# Proj_USB_GPIB.net
KiCad netlist of a schematic drawn in Altium Designer
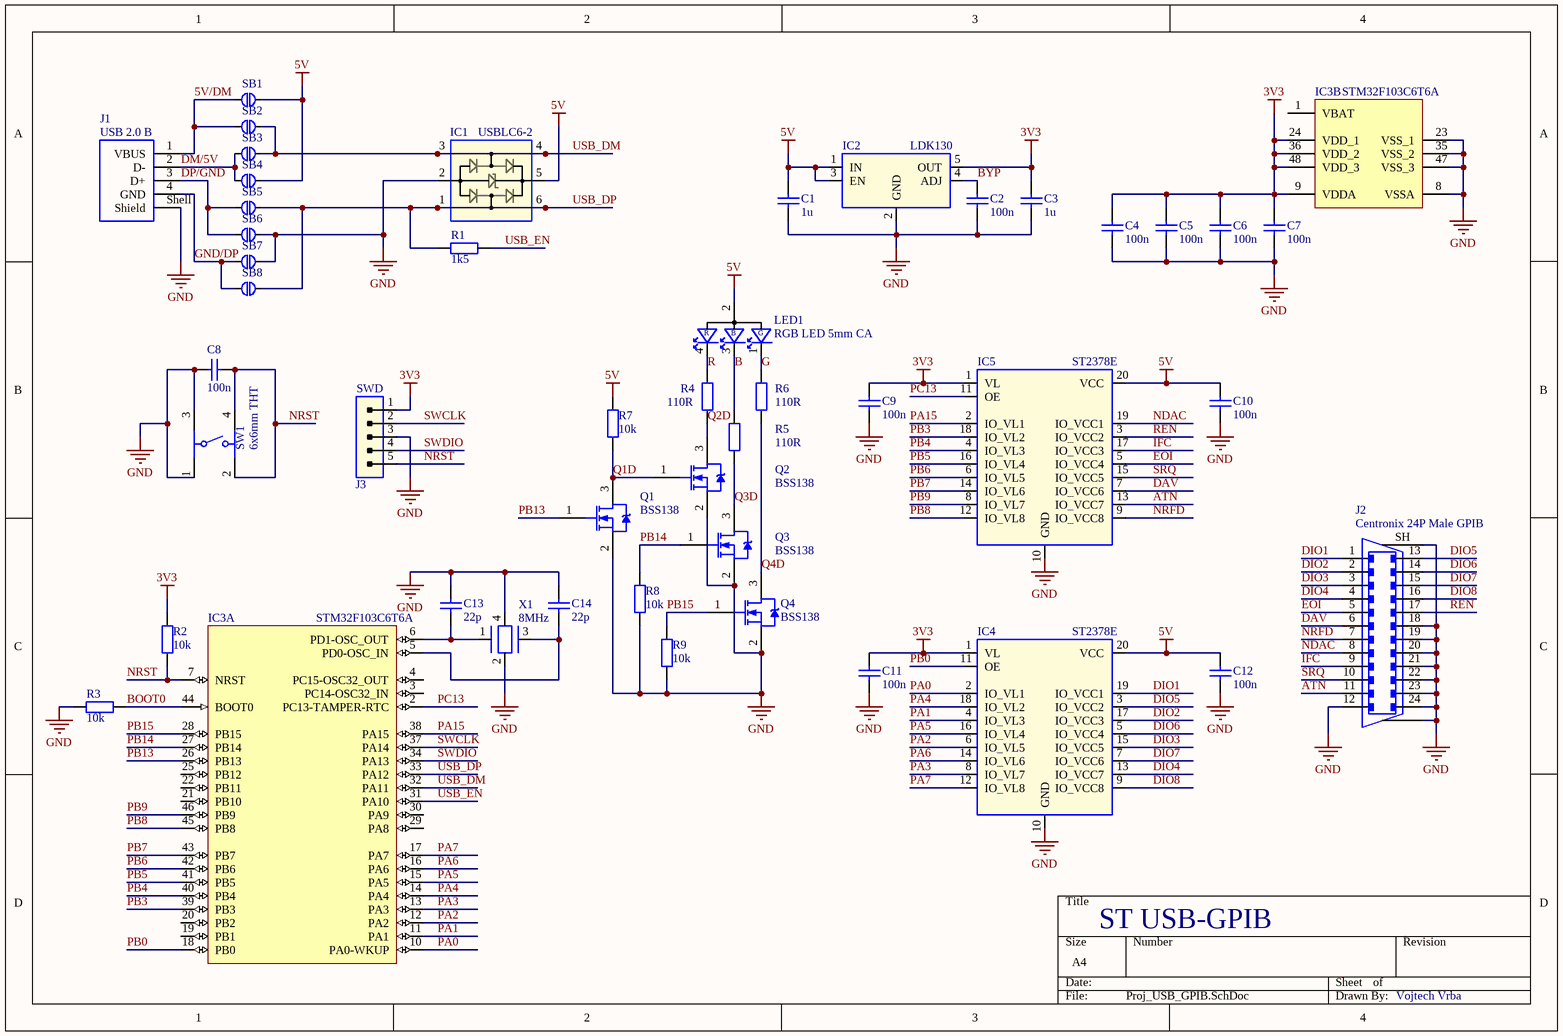
[diagram p0: Proj_USB_GPIB.SchDoc]

(export (version "E")
  (design (tool "Eeschema 10.0.6"))
  (components
    (comp (ref "C1")
      (value "1u")
      (footprint "0603")
      (description "Capacitor")
      (fields (field (name "Comment") "Cap") (field (name "PUBLISHER") "Altium Limited"))
      (libsource (lib "moje") (part "Cap"))
    )
    (comp (ref "C2")
      (value "100n")
      (footprint "0603")
      (description "Capacitor")
      (fields (field (name "Comment") "Cap") (field (name "PUBLISHER") "Altium Limited"))
      (libsource (lib "moje") (part "Cap"))
    )
    (comp (ref "C3")
      (value "1u")
      (footprint "0603")
      (description "Capacitor")
      (fields (field (name "Comment") "Cap") (field (name "PUBLISHER") "Altium Limited"))
      (libsource (lib "moje") (part "Cap"))
    )
    (comp (ref "C4")
      (value "100n")
      (footprint "0603")
      (description "Capacitor")
      (fields (field (name "Comment") "Cap") (field (name "PUBLISHER") "Altium Limited"))
      (libsource (lib "moje") (part "Cap"))
    )
    (comp (ref "C5")
      (value "100n")
      (footprint "0603")
      (description "Capacitor")
      (fields (field (name "Comment") "Cap") (field (name "PUBLISHER") "Altium Limited"))
      (libsource (lib "moje") (part "Cap"))
    )
    (comp (ref "C6")
      (value "100n")
      (footprint "0603")
      (description "Capacitor")
      (fields (field (name "Comment") "Cap") (field (name "PUBLISHER") "Altium Limited"))
      (libsource (lib "moje") (part "Cap"))
    )
    (comp (ref "C7")
      (value "100n")
      (footprint "0603")
      (description "Capacitor")
      (fields (field (name "Comment") "Cap") (field (name "PUBLISHER") "Altium Limited"))
      (libsource (lib "moje") (part "Cap"))
    )
    (comp (ref "C8")
      (value "100n")
      (footprint "0603")
      (description "Capacitor")
      (fields (field (name "Comment") "Cap") (field (name "PUBLISHER") "Altium Limited"))
      (libsource (lib "moje") (part "Cap"))
    )
    (comp (ref "C9")
      (value "100n")
      (footprint "0603")
      (description "Capacitor")
      (fields (field (name "Comment") "Cap") (field (name "PUBLISHER") "Altium Limited"))
      (libsource (lib "moje") (part "Cap"))
    )
    (comp (ref "C10")
      (value "100n")
      (footprint "0603")
      (description "Capacitor")
      (fields (field (name "Comment") "Cap") (field (name "PUBLISHER") "Altium Limited"))
      (libsource (lib "moje") (part "Cap"))
    )
    (comp (ref "C11")
      (value "100n")
      (footprint "0603")
      (description "Capacitor")
      (fields (field (name "Comment") "Cap") (field (name "PUBLISHER") "Altium Limited"))
      (libsource (lib "moje") (part "Cap"))
    )
    (comp (ref "C12")
      (value "100n")
      (footprint "0603")
      (description "Capacitor")
      (fields (field (name "Comment") "Cap") (field (name "PUBLISHER") "Altium Limited"))
      (libsource (lib "moje") (part "Cap"))
    )
    (comp (ref "C13")
      (value "22p")
      (footprint "0603")
      (description "Capacitor")
      (fields (field (name "Comment") "Cap") (field (name "PUBLISHER") "Altium Limited"))
      (libsource (lib "moje") (part "Cap"))
    )
    (comp (ref "C14")
      (value "22p")
      (footprint "0603")
      (description "Capacitor")
      (fields (field (name "Comment") "Cap") (field (name "PUBLISHER") "Altium Limited"))
      (libsource (lib "moje") (part "Cap"))
    )
    (comp (ref "IC1")
      (value "USBLC6-2")
      (footprint "SOT23-6")
      (description "Very low capacitance ESD protection diode array")
      (libsource (lib "moje") (part "USBLC6-2"))
    )
    (comp (ref "IC2")
      (value "LDK130")
      (footprint "SOT23-5")
      (description "300 mA low quiescent current very low noise LDO")
      (libsource (lib "moje") (part "LDK130"))
    )
    (comp (ref "IC3")
      (value "STM32F103C6T6A")
      (footprint "STM-LQFP48_L")
      (libsource (lib "STMicroelectronics STM32 F1") (part "STM32F103C6T6A"))
    )
    (comp (ref "IC4")
      (value "ST2378E")
      (footprint "TSSOP20")
      (description "8-bit dual supply 1.71 V to 5.5 V level translator  with I/O VCC ±15 kV ESD protection")
      (libsource (lib "moje") (part "ST2378E"))
    )
    (comp (ref "IC5")
      (value "ST2378E")
      (footprint "TSSOP20")
      (description "8-bit dual supply 1.71 V to 5.5 V level translator  with I/O VCC ±15 kV ESD protection")
      (libsource (lib "moje") (part "ST2378E"))
    )
    (comp (ref "J1")
      (value "USB 2.0 B")
      (footprint "61400416121")
      (description "USB 2.0 Type B, Receptacle, Horizontal, THT")
      (fields
        (field (name "MANUFACTURER") "Wurth Elektronik")
        (field (name "MANUFACTURER PART NUMBER") "61400416121")
      )
      (libsource (lib "WR-USB (rev21a)") (part "61400416121"))
    )
    (comp (ref "J2")
      (value "Centronix 24P Male GPIB")
      (footprint "Norcomp-112-024-213R001")
      (description "Centronix 24P Male THT GPIB Connector, Farnell 2421095")
      (libsource (lib "moje") (part "Centronix 24P Male GPIB"))
    )
    (comp (ref "J3")
      (value "SWD")
      (footprint "PIN_HEADER_5P")
      (libsource (lib "moje") (part "Pin Header 5P"))
    )
    (comp (ref "LED1")
      (value "RGB LED 5mm CA")
      (footprint "RGB_LED_5mm")
      (description "5mm RGB LED Common Anode, eg. OSTHMA5B61A")
      (libsource (lib "moje") (part "RGB LED 5mm CA"))
    )
    (comp (ref "Q1")
      (value "BSS138")
      (footprint "SOT23-3")
      (description "MOSFET SOT-23 N-CH LOGIC LEVEL")
      (fields (field (name "PUBLISHER") "Altium Limited"))
      (libsource (lib "moje") (part "BSS138"))
    )
    (comp (ref "Q2")
      (value "BSS138")
      (footprint "SOT23-3")
      (description "MOSFET SOT-23 N-CH LOGIC LEVEL")
      (fields (field (name "PUBLISHER") "Altium Limited"))
      (libsource (lib "moje") (part "BSS138"))
    )
    (comp (ref "Q3")
      (value "BSS138")
      (footprint "SOT23-3")
      (description "MOSFET SOT-23 N-CH LOGIC LEVEL")
      (fields (field (name "PUBLISHER") "Altium Limited"))
      (libsource (lib "moje") (part "BSS138"))
    )
    (comp (ref "Q4")
      (value "BSS138")
      (footprint "SOT23-3")
      (description "MOSFET SOT-23 N-CH LOGIC LEVEL")
      (fields (field (name "PUBLISHER") "Altium Limited"))
      (libsource (lib "moje") (part "BSS138"))
    )
    (comp (ref "R1")
      (value "1k5")
      (footprint "0603")
      (description "Resistor")
      (fields (field (name "Comment") "Res") (field (name "PUBLISHER") "Altium Limited"))
      (libsource (lib "") (part "Res_3"))
    )
    (comp (ref "R2")
      (value "10k")
      (footprint "0603")
      (description "Resistor")
      (fields (field (name "Comment") "Res") (field (name "PUBLISHER") "Altium Limited"))
      (libsource (lib "") (part "Res_2"))
    )
    (comp (ref "R3")
      (value "10k")
      (footprint "0603")
      (description "Resistor")
      (fields (field (name "Comment") "Res") (field (name "PUBLISHER") "Altium Limited"))
      (libsource (lib "") (part "Res_1"))
    )
    (comp (ref "R4")
      (value "110R")
      (footprint "0603")
      (description "Resistor")
      (fields (field (name "Comment") "Res") (field (name "PUBLISHER") "Altium Limited"))
      (libsource (lib "") (part "Res_1"))
    )
    (comp (ref "R5")
      (value "110R")
      (footprint "0603")
      (description "Resistor")
      (fields (field (name "Comment") "Res") (field (name "PUBLISHER") "Altium Limited"))
      (libsource (lib "moje") (part "Res"))
    )
    (comp (ref "R6")
      (value "110R")
      (footprint "0603")
      (description "Resistor")
      (fields (field (name "Comment") "Res") (field (name "PUBLISHER") "Altium Limited"))
      (libsource (lib "moje") (part "Res"))
    )
    (comp (ref "R7")
      (value "10k")
      (footprint "0603")
      (description "Resistor")
      (fields (field (name "Comment") "Res") (field (name "PUBLISHER") "Altium Limited"))
      (libsource (lib "") (part "Res_2"))
    )
    (comp (ref "R8")
      (value "10k")
      (footprint "0603")
      (description "Resistor")
      (fields (field (name "Comment") "Res") (field (name "PUBLISHER") "Altium Limited"))
      (libsource (lib "") (part "Res_2"))
    )
    (comp (ref "R9")
      (value "10k")
      (footprint "0603")
      (description "Resistor")
      (fields (field (name "Comment") "Res") (field (name "PUBLISHER") "Altium Limited"))
      (libsource (lib "") (part "Res_2"))
    )
    (comp (ref "SB1") (value "SHORT_CON2") (footprint "0402") (libsource (lib "moje") (part "SHORT_CON2")))
    (comp (ref "SB2") (value "SHORT_CON2") (footprint "0402") (libsource (lib "moje") (part "SHORT_CON2")))
    (comp (ref "SB3") (value "SHORT_CON2") (footprint "0402") (libsource (lib "moje") (part "SHORT_CON2")))
    (comp (ref "SB4") (value "SHORT_CON2") (footprint "0402") (libsource (lib "moje") (part "SHORT_CON2")))
    (comp (ref "SB5") (value "SHORT_CON2") (footprint "0402") (libsource (lib "moje") (part "SHORT_CON2")))
    (comp (ref "SB6") (value "SHORT_CON2") (footprint "0402") (libsource (lib "moje") (part "SHORT_CON2")))
    (comp (ref "SB7") (value "SHORT_CON2") (footprint "0402") (libsource (lib "moje") (part "SHORT_CON2")))
    (comp (ref "SB8") (value "SHORT_CON2") (footprint "0402") (libsource (lib "moje") (part "SHORT_CON2")))
    (comp (ref "SW1")
      (value "6x6mm THT")
      (footprint "4301x60957x6")
      (description "WS-TATV THT Tact Switch 6x6mm, height 9.5mm, 160gf")
      (fields (field (name "PART NUMBER") "430186095716") (field (name "PUBLISHER") "Wurth Elektronik"))
      (libsource (lib "WS-TATV (rev19a)") (part "430186095716"))
    )
    (comp (ref "X1") (value "8MHz") (footprint "CRYSTAL_5x3.2mm") (libsource (lib "moje") (part "Crystal")))
  )
  (nets
    (net (code "1") (name "/5V{slash}DM") (class "Default")
      (node (ref "J1") (pin "1") (pinfunction "VBUS_1") (pintype "passive"))
      (node (ref "SB1") (pin "1") (pinfunction "1_1") (pintype "passive"))
      (node (ref "SB2") (pin "1") (pinfunction "1_1") (pintype "passive"))
    )
    (net (code "2") (name "/ATN") (class "Default")
      (node (ref "IC5") (pin "13") (pinfunction "IO_VCC7_13") (pintype "passive"))
      (node (ref "J2") (pin "11") (pinfunction "11_11") (pintype "passive"))
    )
    (net (code "3") (name "/B") (class "Default")
      (node (ref "LED1") (pin "3") (pinfunction "B_3") (pintype "passive"))
      (node (ref "R5") (pin "1") (pinfunction "1_1") (pintype "passive"))
    )
    (net (code "4") (name "/BOOT0") (class "Default")
      (node (ref "IC3") (pin "44") (pinfunction "BOOT0_44") (pintype "input"))
      (node (ref "R3") (pin "1") (pinfunction "1_1") (pintype "passive"))
    )
    (net (code "5") (name "/BYP") (class "Default")
      (node (ref "C2") (pin "1") (pinfunction "1_1") (pintype "passive"))
      (node (ref "IC2") (pin "4") (pinfunction "ADJ_4") (pintype "passive"))
    )
    (net (code "6") (name "/DAV") (class "Default")
      (node (ref "IC5") (pin "7") (pinfunction "IO_VCC6_7") (pintype "passive"))
      (node (ref "J2") (pin "6") (pinfunction "6_6") (pintype "passive"))
    )
    (net (code "7") (name "/DIO1") (class "Default")
      (node (ref "IC4") (pin "19") (pinfunction "IO_VCC1_19") (pintype "passive"))
      (node (ref "J2") (pin "1") (pinfunction "0_1") (pintype "passive"))
    )
    (net (code "8") (name "/DIO2") (class "Default")
      (node (ref "IC4") (pin "17") (pinfunction "IO_VCC3_17") (pintype "passive"))
      (node (ref "J2") (pin "2") (pinfunction "2_2") (pintype "passive"))
    )
    (net (code "9") (name "/DIO3") (class "Default")
      (node (ref "IC4") (pin "15") (pinfunction "IO_VCC5_15") (pintype "passive"))
      (node (ref "J2") (pin "3") (pinfunction "3_3") (pintype "passive"))
    )
    (net (code "10") (name "/DIO4") (class "Default")
      (node (ref "IC4") (pin "13") (pinfunction "IO_VCC7_13") (pintype "passive"))
      (node (ref "J2") (pin "4") (pinfunction "4_4") (pintype "passive"))
    )
    (net (code "11") (name "/DIO5") (class "Default")
      (node (ref "IC4") (pin "3") (pinfunction "IO_VCC2_3") (pintype "passive"))
      (node (ref "J2") (pin "13") (pinfunction "13_13") (pintype "passive"))
    )
    (net (code "12") (name "/DIO6") (class "Default")
      (node (ref "IC4") (pin "5") (pinfunction "IO_VCC4_5") (pintype "passive"))
      (node (ref "J2") (pin "14") (pinfunction "14_14") (pintype "passive"))
    )
    (net (code "13") (name "/DIO7") (class "Default")
      (node (ref "IC4") (pin "7") (pinfunction "IO_VCC6_7") (pintype "passive"))
      (node (ref "J2") (pin "15") (pinfunction "15_15") (pintype "passive"))
    )
    (net (code "14") (name "/DIO8") (class "Default")
      (node (ref "IC4") (pin "9") (pinfunction "IO_VCC8_9") (pintype "passive"))
      (node (ref "J2") (pin "16") (pinfunction "16_16") (pintype "passive"))
    )
    (net (code "15") (name "/DM{slash}5V") (class "Default")
      (node (ref "J1") (pin "2") (pinfunction "D-_2") (pintype "passive"))
      (node (ref "SB3") (pin "1") (pinfunction "1_1") (pintype "passive"))
      (node (ref "SB4") (pin "1") (pinfunction "1_1") (pintype "passive"))
    )
    (net (code "16") (name "/DP{slash}GND") (class "Default")
      (node (ref "J1") (pin "3") (pinfunction "D+_3") (pintype "passive"))
      (node (ref "SB5") (pin "1") (pinfunction "1_1") (pintype "passive"))
      (node (ref "SB6") (pin "1") (pinfunction "1_1") (pintype "passive"))
    )
    (net (code "17") (name "/EOI") (class "Default")
      (node (ref "IC5") (pin "5") (pinfunction "IO_VCC4_5") (pintype "passive"))
      (node (ref "J2") (pin "5") (pinfunction "5_5") (pintype "passive"))
    )
    (net (code "18") (name "/G") (class "Default")
      (node (ref "LED1") (pin "1") (pinfunction "G_1") (pintype "passive"))
      (node (ref "R6") (pin "1") (pinfunction "1_1") (pintype "passive"))
    )
    (net (code "19") (name "/GND{slash}DP") (class "Default")
      (node (ref "J1") (pin "4") (pinfunction "GND_4") (pintype "passive"))
      (node (ref "SB7") (pin "1") (pinfunction "1_1") (pintype "passive"))
      (node (ref "SB8") (pin "1") (pinfunction "1_1") (pintype "passive"))
    )
    (net (code "20") (name "/IFC") (class "Default")
      (node (ref "IC5") (pin "17") (pinfunction "IO_VCC3_17") (pintype "passive"))
      (node (ref "J2") (pin "9") (pinfunction "9_9") (pintype "passive"))
    )
    (net (code "21") (name "/NDAC") (class "Default")
      (node (ref "IC5") (pin "19") (pinfunction "IO_VCC1_19") (pintype "passive"))
      (node (ref "J2") (pin "8") (pinfunction "8_8") (pintype "passive"))
    )
    (net (code "22") (name "/NRFD") (class "Default")
      (node (ref "IC5") (pin "9") (pinfunction "IO_VCC8_9") (pintype "passive"))
      (node (ref "J2") (pin "7") (pinfunction "7_7") (pintype "passive"))
    )
    (net (code "23") (name "/NRST") (class "Default")
      (node (ref "C8") (pin "2") (pinfunction "2_2") (pintype "passive"))
      (node (ref "IC3") (pin "7") (pinfunction "NRST_7") (pintype "bidirectional"))
      (node (ref "J3") (pin "5") (pinfunction "0_5") (pintype "passive"))
      (node (ref "R2") (pin "1") (pinfunction "1_1") (pintype "passive"))
      (node (ref "SW1") (pin "2") (pinfunction "2_2") (pintype "passive"))
      (node (ref "SW1") (pin "4") (pinfunction "4_4") (pintype "passive"))
    )
    (net (code "24") (name "/PA0") (class "Default")
      (node (ref "IC3") (pin "10") (pinfunction "PA0-WKUP_10") (pintype "bidirectional"))
      (node (ref "IC4") (pin "2") (pinfunction "IO_VL1_2") (pintype "passive"))
    )
    (net (code "25") (name "/PA1") (class "Default")
      (node (ref "IC3") (pin "11") (pinfunction "PA1_11") (pintype "bidirectional"))
      (node (ref "IC4") (pin "4") (pinfunction "IO_VL3_4") (pintype "passive"))
    )
    (net (code "26") (name "/PA2") (class "Default")
      (node (ref "IC3") (pin "12") (pinfunction "PA2_12") (pintype "bidirectional"))
      (node (ref "IC4") (pin "6") (pinfunction "IO_VL5_6") (pintype "passive"))
    )
    (net (code "27") (name "/PA3") (class "Default")
      (node (ref "IC3") (pin "13") (pinfunction "PA3_13") (pintype "bidirectional"))
      (node (ref "IC4") (pin "8") (pinfunction "IO_VL7_8") (pintype "passive"))
    )
    (net (code "28") (name "/PA4") (class "Default")
      (node (ref "IC3") (pin "14") (pinfunction "PA4_14") (pintype "bidirectional"))
      (node (ref "IC4") (pin "18") (pinfunction "IO_VL2_18") (pintype "passive"))
    )
    (net (code "29") (name "/PA5") (class "Default")
      (node (ref "IC3") (pin "15") (pinfunction "PA5_15") (pintype "bidirectional"))
      (node (ref "IC4") (pin "16") (pinfunction "IO_VL4_16") (pintype "passive"))
    )
    (net (code "30") (name "/PA6") (class "Default")
      (node (ref "IC3") (pin "16") (pinfunction "PA6_16") (pintype "bidirectional"))
      (node (ref "IC4") (pin "14") (pinfunction "IO_VL6_14") (pintype "passive"))
    )
    (net (code "31") (name "/PA7") (class "Default")
      (node (ref "IC3") (pin "17") (pinfunction "PA7_17") (pintype "bidirectional"))
      (node (ref "IC4") (pin "12") (pinfunction "IO_VL8_12") (pintype "passive"))
    )
    (net (code "32") (name "/PA15") (class "Default")
      (node (ref "IC3") (pin "38") (pinfunction "PA15_38") (pintype "bidirectional"))
      (node (ref "IC5") (pin "2") (pinfunction "IO_VL1_2") (pintype "passive"))
    )
    (net (code "33") (name "/PB0") (class "Default")
      (node (ref "IC3") (pin "18") (pinfunction "PB0_18") (pintype "bidirectional"))
      (node (ref "IC4") (pin "11") (pinfunction "OE_11") (pintype "passive"))
    )
    (net (code "34") (name "/PB3") (class "Default")
      (node (ref "IC3") (pin "39") (pinfunction "PB3_39") (pintype "bidirectional"))
      (node (ref "IC5") (pin "18") (pinfunction "IO_VL2_18") (pintype "passive"))
    )
    (net (code "35") (name "/PB4") (class "Default")
      (node (ref "IC3") (pin "40") (pinfunction "PB4_40") (pintype "bidirectional"))
      (node (ref "IC5") (pin "4") (pinfunction "IO_VL3_4") (pintype "passive"))
    )
    (net (code "36") (name "/PB5") (class "Default")
      (node (ref "IC3") (pin "41") (pinfunction "PB5_41") (pintype "bidirectional"))
      (node (ref "IC5") (pin "16") (pinfunction "IO_VL4_16") (pintype "passive"))
    )
    (net (code "37") (name "/PB6") (class "Default")
      (node (ref "IC3") (pin "42") (pinfunction "PB6_42") (pintype "bidirectional"))
      (node (ref "IC5") (pin "6") (pinfunction "IO_VL5_6") (pintype "passive"))
    )
    (net (code "38") (name "/PB7") (class "Default")
      (node (ref "IC3") (pin "43") (pinfunction "PB7_43") (pintype "bidirectional"))
      (node (ref "IC5") (pin "14") (pinfunction "IO_VL6_14") (pintype "passive"))
    )
    (net (code "39") (name "/PB8") (class "Default")
      (node (ref "IC3") (pin "45") (pinfunction "PB8_45") (pintype "bidirectional"))
      (node (ref "IC5") (pin "12") (pinfunction "IO_VL8_12") (pintype "passive"))
    )
    (net (code "40") (name "/PB9") (class "Default")
      (node (ref "IC3") (pin "46") (pinfunction "PB9_46") (pintype "bidirectional"))
      (node (ref "IC5") (pin "8") (pinfunction "IO_VL7_8") (pintype "passive"))
    )
    (net (code "41") (name "/PB13") (class "Default")
      (node (ref "IC3") (pin "26") (pinfunction "PB13_26") (pintype "bidirectional"))
      (node (ref "Q1") (pin "1") (pinfunction "G_1") (pintype "passive"))
    )
    (net (code "42") (name "/PB14") (class "Default")
      (node (ref "IC3") (pin "27") (pinfunction "PB14_27") (pintype "bidirectional"))
      (node (ref "Q3") (pin "1") (pinfunction "G_1") (pintype "passive"))
      (node (ref "R8") (pin "2") (pinfunction "2_2") (pintype "passive"))
    )
    (net (code "43") (name "/PB15") (class "Default")
      (node (ref "IC3") (pin "28") (pinfunction "PB15_28") (pintype "bidirectional"))
      (node (ref "Q4") (pin "1") (pinfunction "G_1") (pintype "passive"))
      (node (ref "R9") (pin "2") (pinfunction "2_2") (pintype "passive"))
    )
    (net (code "44") (name "/PC13") (class "Default")
      (node (ref "IC3") (pin "2") (pinfunction "PC13-TAMPER-RTC_2") (pintype "bidirectional"))
      (node (ref "IC5") (pin "11") (pinfunction "OE_11") (pintype "passive"))
    )
    (net (code "45") (name "/Q1D") (class "Default")
      (node (ref "Q1") (pin "3") (pinfunction "D_3") (pintype "passive"))
      (node (ref "Q2") (pin "1") (pinfunction "G_1") (pintype "passive"))
      (node (ref "R7") (pin "1") (pinfunction "1_1") (pintype "passive"))
    )
    (net (code "46") (name "/Q2D") (class "Default")
      (node (ref "Q2") (pin "3") (pinfunction "D_3") (pintype "passive"))
      (node (ref "R4") (pin "2") (pinfunction "2_2") (pintype "passive"))
    )
    (net (code "47") (name "/Q3D") (class "Default")
      (node (ref "Q3") (pin "3") (pinfunction "D_3") (pintype "passive"))
      (node (ref "R5") (pin "2") (pinfunction "2_2") (pintype "passive"))
    )
    (net (code "48") (name "/Q4D") (class "Default")
      (node (ref "Q4") (pin "3") (pinfunction "D_3") (pintype "passive"))
      (node (ref "R6") (pin "2") (pinfunction "2_2") (pintype "passive"))
    )
    (net (code "49") (name "/R") (class "Default")
      (node (ref "LED1") (pin "4") (pinfunction "R_4") (pintype "passive"))
      (node (ref "R4") (pin "1") (pinfunction "1_1") (pintype "passive"))
    )
    (net (code "50") (name "/REN") (class "Default")
      (node (ref "IC5") (pin "3") (pinfunction "IO_VCC2_3") (pintype "passive"))
      (node (ref "J2") (pin "17") (pinfunction "17_17") (pintype "passive"))
    )
    (net (code "51") (name "/SRQ") (class "Default")
      (node (ref "IC5") (pin "15") (pinfunction "IO_VCC5_15") (pintype "passive"))
      (node (ref "J2") (pin "10") (pinfunction "10_10") (pintype "passive"))
    )
    (net (code "52") (name "/SWCLK") (class "Default")
      (node (ref "IC3") (pin "37") (pinfunction "PA14_37") (pintype "bidirectional"))
      (node (ref "J3") (pin "2") (pinfunction "0_2") (pintype "passive"))
    )
    (net (code "53") (name "/SWDIO") (class "Default")
      (node (ref "IC3") (pin "34") (pinfunction "PA13_34") (pintype "bidirectional"))
      (node (ref "J3") (pin "4") (pinfunction "0_4") (pintype "passive"))
    )
    (net (code "54") (name "/USB_DM") (class "Default")
      (node (ref "IC1") (pin "3") (pinfunction "IO_3") (pintype "passive"))
      (node (ref "IC1") (pin "4") (pinfunction "IO_4") (pintype "passive"))
      (node (ref "IC3") (pin "32") (pinfunction "PA11_32") (pintype "bidirectional"))
      (node (ref "SB2") (pin "2") (pinfunction "2_2") (pintype "passive"))
      (node (ref "SB3") (pin "2") (pinfunction "2_2") (pintype "passive"))
    )
    (net (code "55") (name "/USB_DP") (class "Default")
      (node (ref "IC1") (pin "1") (pinfunction "IO_1") (pintype "passive"))
      (node (ref "IC1") (pin "6") (pinfunction "IO_6") (pintype "passive"))
      (node (ref "IC3") (pin "33") (pinfunction "PA12_33") (pintype "bidirectional"))
      (node (ref "R1") (pin "1") (pinfunction "1_1") (pintype "passive"))
      (node (ref "SB5") (pin "2") (pinfunction "2_2") (pintype "passive"))
      (node (ref "SB8") (pin "2") (pinfunction "2_2") (pintype "passive"))
    )
    (net (code "56") (name "/USB_EN") (class "Default")
      (node (ref "IC3") (pin "31") (pinfunction "PA10_31") (pintype "bidirectional"))
      (node (ref "R1") (pin "2") (pinfunction "2_2") (pintype "passive"))
    )
    (net (code "57") (name "3V3") (class "Default")
      (node (ref "C11") (pin "1") (pinfunction "1_1") (pintype "passive"))
      (node (ref "C3") (pin "1") (pinfunction "1_1") (pintype "passive"))
      (node (ref "C4") (pin "1") (pinfunction "1_1") (pintype "passive"))
      (node (ref "C5") (pin "1") (pinfunction "1_1") (pintype "passive"))
      (node (ref "C6") (pin "1") (pinfunction "1_1") (pintype "passive"))
      (node (ref "C7") (pin "1") (pinfunction "1_1") (pintype "passive"))
      (node (ref "C9") (pin "1") (pinfunction "1_1") (pintype "passive"))
      (node (ref "IC2") (pin "5") (pinfunction "OUT_5") (pintype "passive"))
      (node (ref "IC3") (pin "24") (pinfunction "VDD_1_24") (pintype "power_in"))
      (node (ref "IC3") (pin "36") (pinfunction "VDD_2_36") (pintype "power_in"))
      (node (ref "IC3") (pin "48") (pinfunction "VDD_3_48") (pintype "power_in"))
      (node (ref "IC3") (pin "9") (pinfunction "VDDA_9") (pintype "power_in"))
      (node (ref "IC4") (pin "1") (pinfunction "VL_1") (pintype "passive"))
      (node (ref "IC5") (pin "1") (pinfunction "VL_1") (pintype "passive"))
      (node (ref "J3") (pin "1") (pinfunction "0_1") (pintype "passive"))
      (node (ref "R2") (pin "2") (pinfunction "2_2") (pintype "passive"))
    )
    (net (code "58") (name "5V") (class "Default")
      (node (ref "C1") (pin "1") (pinfunction "1_1") (pintype "passive"))
      (node (ref "C10") (pin "1") (pinfunction "1_1") (pintype "passive"))
      (node (ref "C12") (pin "1") (pinfunction "1_1") (pintype "passive"))
      (node (ref "IC1") (pin "5") (pinfunction "VP_5") (pintype "passive"))
      (node (ref "IC2") (pin "1") (pinfunction "IN_1") (pintype "passive"))
      (node (ref "IC2") (pin "3") (pinfunction "EN_3") (pintype "passive"))
      (node (ref "IC4") (pin "20") (pinfunction "VCC_20") (pintype "passive"))
      (node (ref "IC5") (pin "20") (pinfunction "VCC_20") (pintype "passive"))
      (node (ref "LED1") (pin "2") (pinfunction "A_2") (pintype "passive"))
      (node (ref "R7") (pin "2") (pinfunction "2_2") (pintype "passive"))
      (node (ref "SB1") (pin "2") (pinfunction "2_2") (pintype "passive"))
      (node (ref "SB4") (pin "2") (pinfunction "2_2") (pintype "passive"))
    )
    (net (code "59") (name "GND") (class "Default")
      (node (ref "C1") (pin "2") (pinfunction "2_2") (pintype "passive"))
      (node (ref "C10") (pin "2") (pinfunction "2_2") (pintype "passive"))
      (node (ref "C11") (pin "2") (pinfunction "2_2") (pintype "passive"))
      (node (ref "C12") (pin "2") (pinfunction "2_2") (pintype "passive"))
      (node (ref "C13") (pin "2") (pinfunction "2_2") (pintype "passive"))
      (node (ref "C14") (pin "2") (pinfunction "2_2") (pintype "passive"))
      (node (ref "C2") (pin "2") (pinfunction "2_2") (pintype "passive"))
      (node (ref "C3") (pin "2") (pinfunction "2_2") (pintype "passive"))
      (node (ref "C4") (pin "2") (pinfunction "2_2") (pintype "passive"))
      (node (ref "C5") (pin "2") (pinfunction "2_2") (pintype "passive"))
      (node (ref "C6") (pin "2") (pinfunction "2_2") (pintype "passive"))
      (node (ref "C7") (pin "2") (pinfunction "2_2") (pintype "passive"))
      (node (ref "C8") (pin "1") (pinfunction "1_1") (pintype "passive"))
      (node (ref "C9") (pin "2") (pinfunction "2_2") (pintype "passive"))
      (node (ref "IC1") (pin "2") (pinfunction "VN_2") (pintype "passive"))
      (node (ref "IC2") (pin "2") (pinfunction "GND_2") (pintype "passive"))
      (node (ref "IC3") (pin "23") (pinfunction "VSS_1_23") (pintype "power_in"))
      (node (ref "IC3") (pin "35") (pinfunction "VSS_2_35") (pintype "power_in"))
      (node (ref "IC3") (pin "47") (pinfunction "VSS_3_47") (pintype "power_in"))
      (node (ref "IC3") (pin "8") (pinfunction "VSSA_8") (pintype "power_in"))
      (node (ref "IC4") (pin "10") (pinfunction "GND_10") (pintype "passive"))
      (node (ref "IC5") (pin "10") (pinfunction "GND_10") (pintype "passive"))
      (node (ref "J1") (pin "Shell") (pinfunction "Shield_Shell") (pintype "passive"))
      (node (ref "J2") (pin "12") (pinfunction "12_12") (pintype "passive"))
      (node (ref "J2") (pin "18") (pinfunction "18_18") (pintype "passive"))
      (node (ref "J2") (pin "19") (pinfunction "19_19") (pintype "passive"))
      (node (ref "J2") (pin "20") (pinfunction "20_20") (pintype "passive"))
      (node (ref "J2") (pin "21") (pinfunction "21_21") (pintype "passive"))
      (node (ref "J2") (pin "22") (pinfunction "22_22") (pintype "passive"))
      (node (ref "J2") (pin "23") (pinfunction "23_23") (pintype "passive"))
      (node (ref "J2") (pin "24") (pinfunction "24_24") (pintype "passive"))
      (node (ref "J2") (pin "SH") (pinfunction "SH_SH") (pintype "passive"))
      (node (ref "J3") (pin "3") (pinfunction "0_3") (pintype "passive"))
      (node (ref "Q1") (pin "2") (pinfunction "S_2") (pintype "passive"))
      (node (ref "Q2") (pin "2") (pinfunction "S_2") (pintype "passive"))
      (node (ref "Q3") (pin "2") (pinfunction "S_2") (pintype "passive"))
      (node (ref "Q4") (pin "2") (pinfunction "S_2") (pintype "passive"))
      (node (ref "R3") (pin "2") (pinfunction "2_2") (pintype "passive"))
      (node (ref "R8") (pin "1") (pinfunction "1_1") (pintype "passive"))
      (node (ref "R9") (pin "1") (pinfunction "1_1") (pintype "passive"))
      (node (ref "SB6") (pin "2") (pinfunction "2_2") (pintype "passive"))
      (node (ref "SB7") (pin "2") (pinfunction "2_2") (pintype "passive"))
      (node (ref "SW1") (pin "1") (pinfunction "1_1") (pintype "passive"))
      (node (ref "SW1") (pin "3") (pinfunction "3_3") (pintype "passive"))
      (node (ref "X1") (pin "2") (pinfunction "2_2") (pintype "passive"))
      (node (ref "X1") (pin "4") (pinfunction "4_4") (pintype "passive"))
    )
    (net (code "60") (name "Net-(IC3A-PD0-OSC_IN)") (class "Default")
      (node (ref "C14") (pin "1") (pinfunction "1_1") (pintype "passive"))
      (node (ref "IC3") (pin "5") (pinfunction "PD0-OSC_IN_5") (pintype "bidirectional"))
      (node (ref "X1") (pin "3") (pinfunction "3_3") (pintype "passive"))
    )
    (net (code "61") (name "Net-(IC3A-PD1-OSC_OUT)") (class "Default")
      (node (ref "C13") (pin "1") (pinfunction "1_1") (pintype "passive"))
      (node (ref "IC3") (pin "6") (pinfunction "PD1-OSC_OUT_6") (pintype "bidirectional"))
      (node (ref "X1") (pin "1") (pinfunction "1_1") (pintype "passive"))
    )
    (net (code "62") (name "unconnected-(IC3A-PA8-Pad29)") (class "Default")
      (node (ref "IC3") (pin "29") (pinfunction "PA8_29") (pintype "bidirectional"))
    )
    (net (code "63") (name "unconnected-(IC3A-PA9-Pad30)") (class "Default")
      (node (ref "IC3") (pin "30") (pinfunction "PA9_30") (pintype "bidirectional"))
    )
    (net (code "64") (name "unconnected-(IC3A-PB1-Pad19)") (class "Default")
      (node (ref "IC3") (pin "19") (pinfunction "PB1_19") (pintype "bidirectional"))
    )
    (net (code "65") (name "unconnected-(IC3A-PB2-Pad20)") (class "Default")
      (node (ref "IC3") (pin "20") (pinfunction "PB2_20") (pintype "bidirectional"))
    )
    (net (code "66") (name "unconnected-(IC3A-PB10-Pad21)") (class "Default")
      (node (ref "IC3") (pin "21") (pinfunction "PB10_21") (pintype "bidirectional"))
    )
    (net (code "67") (name "unconnected-(IC3A-PB11-Pad22)") (class "Default")
      (node (ref "IC3") (pin "22") (pinfunction "PB11_22") (pintype "bidirectional"))
    )
    (net (code "68") (name "unconnected-(IC3A-PB12-Pad25)") (class "Default")
      (node (ref "IC3") (pin "25") (pinfunction "PB12_25") (pintype "bidirectional"))
    )
    (net (code "69") (name "unconnected-(IC3A-PC14-OSC32_IN-Pad3)") (class "Default")
      (node (ref "IC3") (pin "3") (pinfunction "PC14-OSC32_IN_3") (pintype "bidirectional"))
    )
    (net (code "70") (name "unconnected-(IC3A-PC15-OSC32_OUT-Pad4)") (class "Default")
      (node (ref "IC3") (pin "4") (pinfunction "PC15-OSC32_OUT_4") (pintype "bidirectional"))
    )
    (net (code "71") (name "unconnected-(IC3B-VBAT-Pad1)") (class "Default")
      (node (ref "IC3") (pin "1") (pinfunction "VBAT_1") (pintype "power_in"))
    )
  )
)
